# arm-pro-mini.net
KiCad netlist of a schematic drawn in EAGLE
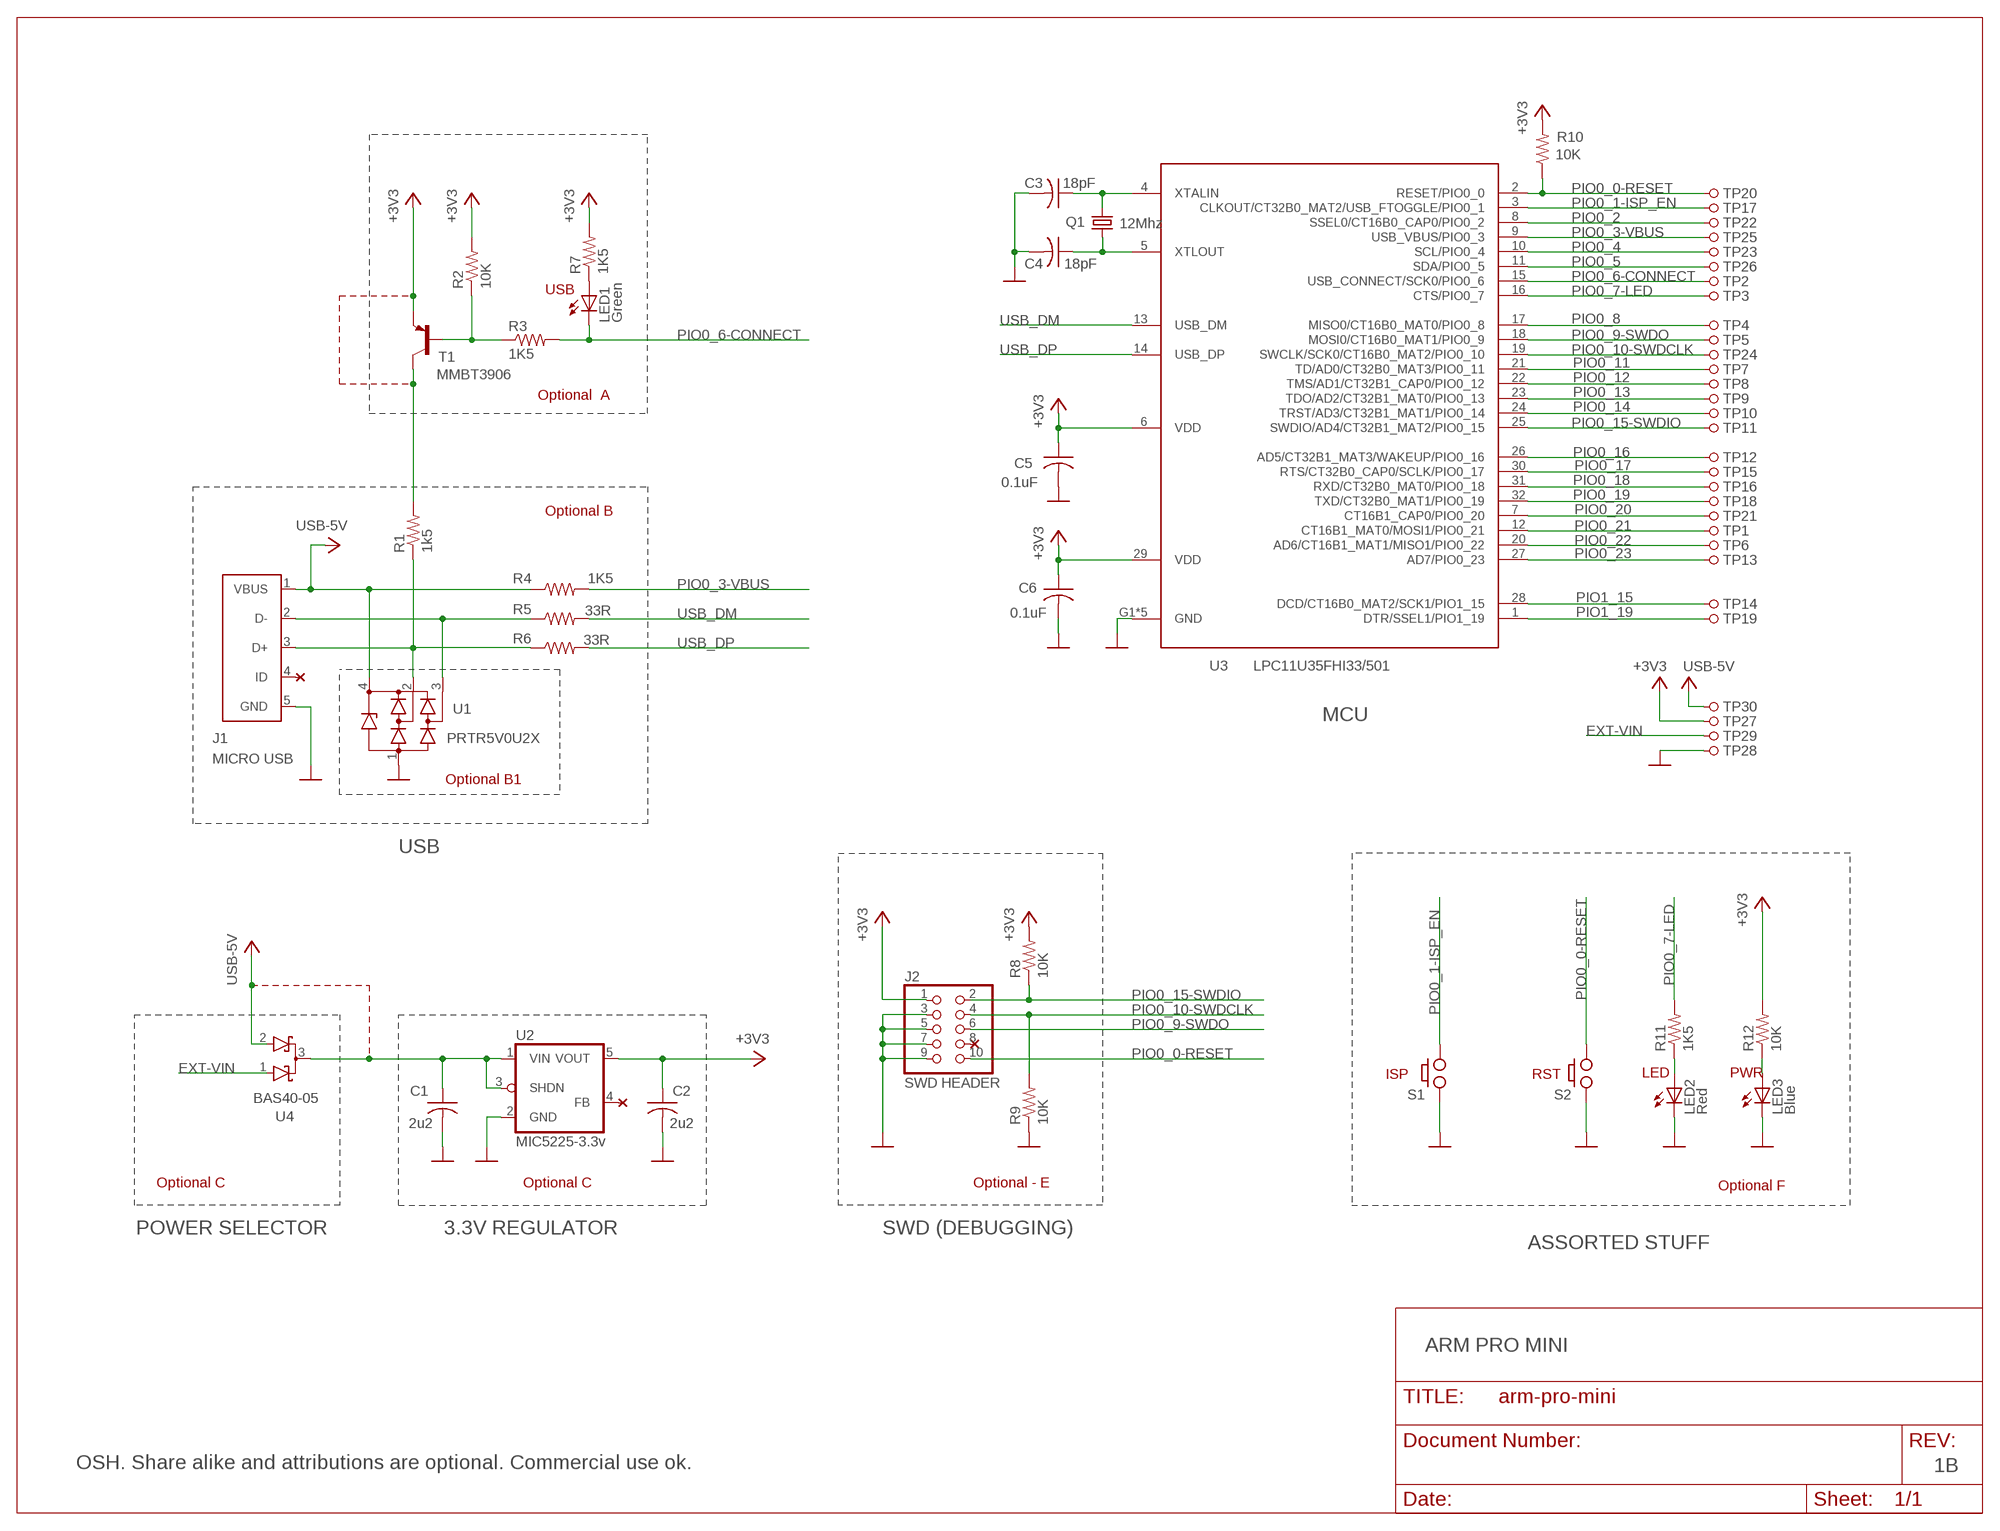
[diagram p0: schematic, sheet 1]

(export (version "E")
  (design (tool "Eeschema 10.0.6"))
  (components
    (comp (ref "C1")
      (value "2u2")
      (footprint "eagle-import:C0603K")
      (libsource (lib "eagle-import") (part "CAPACITORC0603K"))
    )
    (comp (ref "C2")
      (value "2u2")
      (footprint "eagle-import:C0603K")
      (libsource (lib "eagle-import") (part "CAPACITORC0603K"))
    )
    (comp (ref "C3")
      (value "18pF")
      (footprint "eagle-import:C0402K")
      (libsource (lib "eagle-import") (part "C-USC0402K"))
    )
    (comp (ref "C4")
      (value "18pF")
      (footprint "eagle-import:C0402K")
      (libsource (lib "eagle-import") (part "C-USC0402K"))
    )
    (comp (ref "C5")
      (value "0.1uF")
      (footprint "eagle-import:C0603K")
      (libsource (lib "eagle-import") (part "CAPACITORC0603K"))
    )
    (comp (ref "C6")
      (value "0.1uF")
      (footprint "eagle-import:C0603K")
      (libsource (lib "eagle-import") (part "CAPACITORC0603K"))
    )
    (comp (ref "J1")
      (value "MICRO USB")
      (footprint "eagle-import:USB-MICRO-ZX62RD-AB-5P8")
      (libsource (lib "eagle-import") (part "USB"))
    )
    (comp (ref "J2")
      (value "SWD HEADER")
      (footprint "eagle-import:SWD-HEADER")
      (libsource (lib "eagle-import") (part "SWD-HEADER"))
    )
    (comp (ref "LED1")
      (value "Green")
      (footprint "eagle-import:CHIP-LED0603")
      (libsource (lib "eagle-import") (part "LEDCHIP-LED0603"))
    )
    (comp (ref "LED2")
      (value "Red")
      (footprint "eagle-import:CHIP-LED0603")
      (libsource (lib "eagle-import") (part "LEDCHIP-LED0603"))
    )
    (comp (ref "LED3")
      (value "Blue")
      (footprint "eagle-import:CHIP-LED0603")
      (libsource (lib "eagle-import") (part "LEDCHIP-LED0603"))
    )
    (comp (ref "Q1")
      (value "12Mhz")
      (footprint "eagle-import:CRYSTAL")
      (libsource (lib "eagle-import") (part "CRYSTALCTS406"))
    )
    (comp (ref "R1")
      (value "1k5")
      (footprint "eagle-import:R0402")
      (libsource (lib "eagle-import") (part "R-US_R0402"))
    )
    (comp (ref "R2")
      (value "10K")
      (footprint "eagle-import:R0402")
      (libsource (lib "eagle-import") (part "R-US_R0402"))
    )
    (comp (ref "R3")
      (value "1K5")
      (footprint "eagle-import:R0402")
      (libsource (lib "eagle-import") (part "R-US_R0402"))
    )
    (comp (ref "R4")
      (value "1K5")
      (footprint "eagle-import:R0402")
      (libsource (lib "eagle-import") (part "R-US_R0402"))
    )
    (comp (ref "R5")
      (value "33R")
      (footprint "eagle-import:R0402")
      (libsource (lib "eagle-import") (part "R-US_R0402"))
    )
    (comp (ref "R6")
      (value "33R")
      (footprint "eagle-import:R0402")
      (libsource (lib "eagle-import") (part "R-US_R0402"))
    )
    (comp (ref "R7")
      (value "1K5")
      (footprint "eagle-import:R0402")
      (libsource (lib "eagle-import") (part "R-US_R0402"))
    )
    (comp (ref "R8")
      (value "10K")
      (footprint "eagle-import:R0402")
      (libsource (lib "eagle-import") (part "R-US_R0402"))
    )
    (comp (ref "R9")
      (value "10K")
      (footprint "eagle-import:R0402")
      (libsource (lib "eagle-import") (part "R-US_R0402"))
    )
    (comp (ref "R10")
      (value "10K")
      (footprint "eagle-import:R0402")
      (libsource (lib "eagle-import") (part "R-US_R0402"))
    )
    (comp (ref "R11")
      (value "1K5")
      (footprint "eagle-import:R0402")
      (libsource (lib "eagle-import") (part "R-US_R0402"))
    )
    (comp (ref "R12")
      (value "10K")
      (footprint "eagle-import:R0402")
      (libsource (lib "eagle-import") (part "R-US_R0402"))
    )
    (comp (ref "S1")
      (value "PUSH_BUTTON")
      (footprint "eagle-import:PUSH_BUTTON")
      (libsource (lib "eagle-import") (part "PUSH_BUTTON"))
    )
    (comp (ref "S2")
      (value "PUSH_BUTTON")
      (footprint "eagle-import:PUSH_BUTTON")
      (libsource (lib "eagle-import") (part "PUSH_BUTTON"))
    )
    (comp (ref "T1")
      (value "MMBT3906")
      (footprint "eagle-import:SOT23-BEC")
      (libsource (lib "eagle-import") (part "-PNP-SOT23-BECBC857B"))
    )
    (comp (ref "TP1")
      (value "HDR1")
      (footprint "eagle-import:1X01-SQUARE")
      (libsource (lib "eagle-import") (part "PINHD-1X1SQUARE"))
    )
    (comp (ref "TP2")
      (value "HDR1")
      (footprint "eagle-import:1X01")
      (libsource (lib "eagle-import") (part "PINHD-1X1"))
    )
    (comp (ref "TP3")
      (value "HDR1")
      (footprint "eagle-import:1X01")
      (libsource (lib "eagle-import") (part "PINHD-1X1"))
    )
    (comp (ref "TP4")
      (value "HDR1")
      (footprint "eagle-import:1X01")
      (libsource (lib "eagle-import") (part "PINHD-1X1"))
    )
    (comp (ref "TP5")
      (value "HDR1")
      (footprint "eagle-import:1X01")
      (libsource (lib "eagle-import") (part "PINHD-1X1"))
    )
    (comp (ref "TP6")
      (value "HDR1")
      (footprint "eagle-import:1X01")
      (libsource (lib "eagle-import") (part "PINHD-1X1"))
    )
    (comp (ref "TP7")
      (value "HDR1")
      (footprint "eagle-import:1X01")
      (libsource (lib "eagle-import") (part "PINHD-1X1"))
    )
    (comp (ref "TP8")
      (value "HDR1")
      (footprint "eagle-import:1X01")
      (libsource (lib "eagle-import") (part "PINHD-1X1"))
    )
    (comp (ref "TP9")
      (value "HDR1")
      (footprint "eagle-import:1X01")
      (libsource (lib "eagle-import") (part "PINHD-1X1"))
    )
    (comp (ref "TP10")
      (value "HDR1")
      (footprint "eagle-import:1X01")
      (libsource (lib "eagle-import") (part "PINHD-1X1"))
    )
    (comp (ref "TP11")
      (value "HDR1")
      (footprint "eagle-import:1X01")
      (libsource (lib "eagle-import") (part "PINHD-1X1"))
    )
    (comp (ref "TP12")
      (value "HDR1")
      (footprint "eagle-import:1X01")
      (libsource (lib "eagle-import") (part "PINHD-1X1"))
    )
    (comp (ref "TP13")
      (value "HDR1")
      (footprint "eagle-import:1X01")
      (libsource (lib "eagle-import") (part "PINHD-1X1"))
    )
    (comp (ref "TP14")
      (value "HDR1")
      (footprint "eagle-import:1X01")
      (libsource (lib "eagle-import") (part "PINHD-1X1"))
    )
    (comp (ref "TP15")
      (value "HDR1")
      (footprint "eagle-import:1X01")
      (libsource (lib "eagle-import") (part "PINHD-1X1"))
    )
    (comp (ref "TP16")
      (value "HDR1")
      (footprint "eagle-import:1X01")
      (libsource (lib "eagle-import") (part "PINHD-1X1"))
    )
    (comp (ref "TP17")
      (value "HDR1")
      (footprint "eagle-import:1X01")
      (libsource (lib "eagle-import") (part "PINHD-1X1"))
    )
    (comp (ref "TP18")
      (value "HDR1")
      (footprint "eagle-import:1X01")
      (libsource (lib "eagle-import") (part "PINHD-1X1"))
    )
    (comp (ref "TP19")
      (value "HDR1")
      (footprint "eagle-import:1X01")
      (libsource (lib "eagle-import") (part "PINHD-1X1"))
    )
    (comp (ref "TP20")
      (value "HDR1")
      (footprint "eagle-import:1X01")
      (libsource (lib "eagle-import") (part "PINHD-1X1"))
    )
    (comp (ref "TP21")
      (value "HDR1")
      (footprint "eagle-import:1X01")
      (libsource (lib "eagle-import") (part "PINHD-1X1"))
    )
    (comp (ref "TP22")
      (value "HDR1")
      (footprint "eagle-import:1X01")
      (libsource (lib "eagle-import") (part "PINHD-1X1"))
    )
    (comp (ref "TP23")
      (value "HDR1")
      (footprint "eagle-import:1X01")
      (libsource (lib "eagle-import") (part "PINHD-1X1"))
    )
    (comp (ref "TP24")
      (value "HDR1")
      (footprint "eagle-import:1X01")
      (libsource (lib "eagle-import") (part "PINHD-1X1"))
    )
    (comp (ref "TP25")
      (value "HDR1")
      (footprint "eagle-import:1X01")
      (libsource (lib "eagle-import") (part "PINHD-1X1"))
    )
    (comp (ref "TP26")
      (value "HDR1")
      (footprint "eagle-import:1X01")
      (libsource (lib "eagle-import") (part "PINHD-1X1"))
    )
    (comp (ref "TP27")
      (value "HDR1")
      (footprint "eagle-import:1X01")
      (libsource (lib "eagle-import") (part "PINHD-1X1"))
    )
    (comp (ref "TP28")
      (value "HDR1")
      (footprint "eagle-import:1X01")
      (libsource (lib "eagle-import") (part "PINHD-1X1"))
    )
    (comp (ref "TP29")
      (value "HDR1")
      (footprint "eagle-import:1X01")
      (libsource (lib "eagle-import") (part "PINHD-1X1"))
    )
    (comp (ref "TP30")
      (value "HDR1")
      (footprint "eagle-import:1X01")
      (libsource (lib "eagle-import") (part "PINHD-1X1"))
    )
    (comp (ref "U1")
      (value "PRTR5V0U2X")
      (footprint "eagle-import:SOT143B")
      (libsource (lib "eagle-import") (part "PRTR5V0U2X"))
    )
    (comp (ref "U2")
      (value "MIC5225-3.3v")
      (footprint "eagle-import:SOT25")
      (libsource (lib "eagle-import") (part "TC1015"))
    )
    (comp (ref "U3")
      (value "LPC11U35FHI33/501")
      (footprint "eagle-import:HVQFN33-5MM")
      (libsource (lib "eagle-import") (part "LPC11U35FHN33/501"))
    )
    (comp (ref "U4")
      (value "BAS40-05")
      (footprint "eagle-import:SOT23")
      (libsource (lib "eagle-import") (part "BAS40-05"))
    )
  )
  (nets
    (net (code "1") (name "+3V3") (class "Default")
      (node (ref "C2") (pin "1") (pinfunction "1_1") (pintype "passive"))
      (node (ref "C5") (pin "1") (pinfunction "1_1") (pintype "passive"))
      (node (ref "C6") (pin "1") (pinfunction "1_1") (pintype "passive"))
      (node (ref "J2") (pin "1") (pinfunction "1_1") (pintype "passive"))
      (node (ref "R10") (pin "2") (pinfunction "2_2") (pintype "passive"))
      (node (ref "R12") (pin "2") (pinfunction "2_2") (pintype "passive"))
      (node (ref "R2") (pin "2") (pinfunction "2_2") (pintype "passive"))
      (node (ref "R7") (pin "2") (pinfunction "2_2") (pintype "passive"))
      (node (ref "R8") (pin "2") (pinfunction "2_2") (pintype "passive"))
      (node (ref "T1") (pin "E") (pinfunction "E_E") (pintype "passive"))
      (node (ref "TP27") (pin "1") (pinfunction "1_1") (pintype "passive"))
      (node (ref "U2") (pin "5") (pinfunction "VOUT_5") (pintype "power_in"))
      (node (ref "U3") (pin "29") (pinfunction "VDD_29") (pintype "bidirectional"))
      (node (ref "U3") (pin "6") (pinfunction "VDD_6") (pintype "bidirectional"))
    )
    (net (code "2") (name "/EXT-VIN") (class "Default")
      (node (ref "TP29") (pin "1") (pinfunction "1_1") (pintype "passive"))
      (node (ref "U4") (pin "1") (pinfunction "A1_1") (pintype "passive"))
    )
    (net (code "3") (name "/PIO0_0-RESET") (class "Default")
      (node (ref "J2") (pin "10") (pinfunction "10_10") (pintype "passive"))
      (node (ref "R10") (pin "1") (pinfunction "1_1") (pintype "passive"))
      (node (ref "S2") (pin "B2") (pinfunction "2_B2") (pintype "passive"))
      (node (ref "TP20") (pin "1") (pinfunction "1_1") (pintype "passive"))
      (node (ref "U3") (pin "2") (pinfunction "RESET/PIO0_0_2") (pintype "bidirectional"))
    )
    (net (code "4") (name "/PIO0_1-ISP_EN") (class "Default")
      (node (ref "S1") (pin "B2") (pinfunction "2_B2") (pintype "passive"))
      (node (ref "TP17") (pin "1") (pinfunction "1_1") (pintype "passive"))
      (node (ref "U3") (pin "3") (pinfunction "CLKOUT/CT32B0_MAT2/USB_FTOGGLE/PIO0_1_3") (pintype "bidirectional"))
    )
    (net (code "5") (name "/PIO0_2") (class "Default")
      (node (ref "TP22") (pin "1") (pinfunction "1_1") (pintype "passive"))
      (node (ref "U3") (pin "8") (pinfunction "SSEL0/CT16B0_CAP0/PIO0_2_8") (pintype "bidirectional"))
    )
    (net (code "6") (name "/PIO0_3-VBUS") (class "Default")
      (node (ref "R4") (pin "2") (pinfunction "2_2") (pintype "passive"))
      (node (ref "TP25") (pin "1") (pinfunction "1_1") (pintype "passive"))
      (node (ref "U3") (pin "9") (pinfunction "USB_VBUS/PIO0_3_9") (pintype "bidirectional"))
    )
    (net (code "7") (name "/PIO0_4") (class "Default")
      (node (ref "TP23") (pin "1") (pinfunction "1_1") (pintype "passive"))
      (node (ref "U3") (pin "10") (pinfunction "SCL/PIO0_4_10") (pintype "bidirectional"))
    )
    (net (code "8") (name "/PIO0_5") (class "Default")
      (node (ref "TP26") (pin "1") (pinfunction "1_1") (pintype "passive"))
      (node (ref "U3") (pin "11") (pinfunction "SDA/PIO0_5_11") (pintype "bidirectional"))
    )
    (net (code "9") (name "/PIO0_6-CONNECT") (class "Default")
      (node (ref "LED1") (pin "C") (pinfunction "C_C") (pintype "passive"))
      (node (ref "R3") (pin "2") (pinfunction "2_2") (pintype "passive"))
      (node (ref "TP2") (pin "1") (pinfunction "1_1") (pintype "passive"))
      (node (ref "U3") (pin "15") (pinfunction "USB_CONNECT/SCK0/PIO0_6_15") (pintype "bidirectional"))
    )
    (net (code "10") (name "/PIO0_7-LED") (class "Default")
      (node (ref "R11") (pin "2") (pinfunction "2_2") (pintype "passive"))
      (node (ref "TP3") (pin "1") (pinfunction "1_1") (pintype "passive"))
      (node (ref "U3") (pin "16") (pinfunction "CTS/PIO0_7_16") (pintype "bidirectional"))
    )
    (net (code "11") (name "/PIO0_8") (class "Default")
      (node (ref "TP4") (pin "1") (pinfunction "1_1") (pintype "passive"))
      (node (ref "U3") (pin "17") (pinfunction "MISO0/CT16B0_MAT0/PIO0_8_17") (pintype "bidirectional"))
    )
    (net (code "12") (name "/PIO0_9-SWDO") (class "Default")
      (node (ref "J2") (pin "6") (pinfunction "6_6") (pintype "passive"))
      (node (ref "TP5") (pin "1") (pinfunction "1_1") (pintype "passive"))
      (node (ref "U3") (pin "18") (pinfunction "MOSI0/CT16B0_MAT1/PIO0_9_18") (pintype "bidirectional"))
    )
    (net (code "13") (name "/PIO0_10-SWDCLK") (class "Default")
      (node (ref "J2") (pin "4") (pinfunction "4_4") (pintype "passive"))
      (node (ref "R9") (pin "2") (pinfunction "2_2") (pintype "passive"))
      (node (ref "TP24") (pin "1") (pinfunction "1_1") (pintype "passive"))
      (node (ref "U3") (pin "19") (pinfunction "SWCLK/SCK0/CT16B0_MAT2/PIO0_10_19") (pintype "bidirectional"))
    )
    (net (code "14") (name "/PIO0_11") (class "Default")
      (node (ref "TP7") (pin "1") (pinfunction "1_1") (pintype "passive"))
      (node (ref "U3") (pin "21") (pinfunction "TD/AD0/CT32B0_MAT3/PIO0_11_21") (pintype "bidirectional"))
    )
    (net (code "15") (name "/PIO0_12") (class "Default")
      (node (ref "TP8") (pin "1") (pinfunction "1_1") (pintype "passive"))
      (node (ref "U3") (pin "22") (pinfunction "TMS/AD1/CT32B1_CAP0/PIO0_12_22") (pintype "bidirectional"))
    )
    (net (code "16") (name "/PIO0_13") (class "Default")
      (node (ref "TP9") (pin "1") (pinfunction "1_1") (pintype "passive"))
      (node (ref "U3") (pin "23") (pinfunction "TDO/AD2/CT32B1_MAT0/PIO0_13_23") (pintype "bidirectional"))
    )
    (net (code "17") (name "/PIO0_14") (class "Default")
      (node (ref "TP10") (pin "1") (pinfunction "1_1") (pintype "passive"))
      (node (ref "U3") (pin "24") (pinfunction "TRST/AD3/CT32B1_MAT1/PIO0_14_24") (pintype "bidirectional"))
    )
    (net (code "18") (name "/PIO0_15-SWDIO") (class "Default")
      (node (ref "J2") (pin "2") (pinfunction "2_2") (pintype "passive"))
      (node (ref "R8") (pin "1") (pinfunction "1_1") (pintype "passive"))
      (node (ref "TP11") (pin "1") (pinfunction "1_1") (pintype "passive"))
      (node (ref "U3") (pin "25") (pinfunction "SWDIO/AD4/CT32B1_MAT2/PIO0_15_25") (pintype "bidirectional"))
    )
    (net (code "19") (name "/PIO0_16") (class "Default")
      (node (ref "TP12") (pin "1") (pinfunction "1_1") (pintype "passive"))
      (node (ref "U3") (pin "26") (pinfunction "AD5/CT32B1_MAT3/WAKEUP/PIO0_16_26") (pintype "bidirectional"))
    )
    (net (code "20") (name "/PIO0_17") (class "Default")
      (node (ref "TP15") (pin "1") (pinfunction "1_1") (pintype "passive"))
      (node (ref "U3") (pin "30") (pinfunction "RTS/CT32B0_CAP0/SCLK/PIO0_17_30") (pintype "bidirectional"))
    )
    (net (code "21") (name "/PIO0_18") (class "Default")
      (node (ref "TP16") (pin "1") (pinfunction "1_1") (pintype "passive"))
      (node (ref "U3") (pin "31") (pinfunction "RXD/CT32B0_MAT0/PIO0_18_31") (pintype "bidirectional"))
    )
    (net (code "22") (name "/PIO0_19") (class "Default")
      (node (ref "TP18") (pin "1") (pinfunction "1_1") (pintype "passive"))
      (node (ref "U3") (pin "32") (pinfunction "TXD/CT32B0_MAT1/PIO0_19_32") (pintype "bidirectional"))
    )
    (net (code "23") (name "/PIO0_20") (class "Default")
      (node (ref "TP21") (pin "1") (pinfunction "1_1") (pintype "passive"))
      (node (ref "U3") (pin "7") (pinfunction "CT16B1_CAP0/PIO0_20_7") (pintype "bidirectional"))
    )
    (net (code "24") (name "/PIO0_21") (class "Default")
      (node (ref "TP1") (pin "1") (pinfunction "1_1") (pintype "passive"))
      (node (ref "U3") (pin "12") (pinfunction "CT16B1_MAT0/MOSI1/PIO0_21_12") (pintype "bidirectional"))
    )
    (net (code "25") (name "/PIO0_22") (class "Default")
      (node (ref "TP6") (pin "1") (pinfunction "1_1") (pintype "passive"))
      (node (ref "U3") (pin "20") (pinfunction "AD6/CT16B1_MAT1/MISO1/PIO0_22_20") (pintype "bidirectional"))
    )
    (net (code "26") (name "/PIO0_23") (class "Default")
      (node (ref "TP13") (pin "1") (pinfunction "1_1") (pintype "passive"))
      (node (ref "U3") (pin "27") (pinfunction "AD7/PIO0_23_27") (pintype "bidirectional"))
    )
    (net (code "27") (name "/PIO1_15") (class "Default")
      (node (ref "TP14") (pin "1") (pinfunction "1_1") (pintype "passive"))
      (node (ref "U3") (pin "28") (pinfunction "DCD/CT16B0_MAT2/SCK1/PIO1_15_28") (pintype "bidirectional"))
    )
    (net (code "28") (name "/PIO1_19") (class "Default")
      (node (ref "TP19") (pin "1") (pinfunction "1_1") (pintype "passive"))
      (node (ref "U3") (pin "1") (pinfunction "DTR/SSEL1/PIO1_19_1") (pintype "bidirectional"))
    )
    (net (code "29") (name "/USB_DM") (class "Default")
      (node (ref "R5") (pin "2") (pinfunction "2_2") (pintype "passive"))
      (node (ref "U3") (pin "13") (pinfunction "USB_DM_13") (pintype "bidirectional"))
    )
    (net (code "30") (name "/USB_DP") (class "Default")
      (node (ref "R6") (pin "2") (pinfunction "2_2") (pintype "passive"))
      (node (ref "U3") (pin "14") (pinfunction "USB_DP_14") (pintype "bidirectional"))
    )
    (net (code "31") (name "GND") (class "Default")
      (node (ref "C1") (pin "2") (pinfunction "2_2") (pintype "passive"))
      (node (ref "C2") (pin "2") (pinfunction "2_2") (pintype "passive"))
      (node (ref "C3") (pin "2") (pinfunction "2_2") (pintype "passive"))
      (node (ref "C4") (pin "2") (pinfunction "2_2") (pintype "passive"))
      (node (ref "C5") (pin "2") (pinfunction "2_2") (pintype "passive"))
      (node (ref "C6") (pin "2") (pinfunction "2_2") (pintype "passive"))
      (node (ref "J1") (pin "5") (pinfunction "GND_5") (pintype "bidirectional"))
      (node (ref "J2") (pin "3") (pinfunction "3_3") (pintype "passive"))
      (node (ref "J2") (pin "5") (pinfunction "5_5") (pintype "passive"))
      (node (ref "J2") (pin "7") (pinfunction "7_7") (pintype "passive"))
      (node (ref "J2") (pin "9") (pinfunction "9_9") (pintype "passive"))
      (node (ref "LED2") (pin "C") (pinfunction "C_C") (pintype "passive"))
      (node (ref "LED3") (pin "C") (pinfunction "C_C") (pintype "passive"))
      (node (ref "R9") (pin "1") (pinfunction "1_1") (pintype "passive"))
      (node (ref "S1") (pin "A1") (pinfunction "1_A1") (pintype "passive"))
      (node (ref "S2") (pin "A1") (pinfunction "1_A1") (pintype "passive"))
      (node (ref "TP28") (pin "1") (pinfunction "1_1") (pintype "passive"))
      (node (ref "U1") (pin "1") (pinfunction "GND_1") (pintype "passive"))
      (node (ref "U2") (pin "2") (pinfunction "GND_2") (pintype "power_in"))
      (node (ref "U3") (pin "G1") (pinfunction "GND_G1") (pintype "bidirectional"))
      (node (ref "U3") (pin "G2") (pinfunction "GND_G2") (pintype "bidirectional"))
      (node (ref "U3") (pin "G3") (pinfunction "GND_G3") (pintype "bidirectional"))
      (node (ref "U3") (pin "G4") (pinfunction "GND_G4") (pintype "bidirectional"))
      (node (ref "U3") (pin "TAB") (pinfunction "GND_TAB") (pintype "bidirectional"))
    )
    (net (code "32") (name "Net-(J1-D+)") (class "Default")
      (node (ref "J1") (pin "3") (pinfunction "D+_3") (pintype "bidirectional"))
      (node (ref "R1") (pin "1") (pinfunction "1_1") (pintype "passive"))
      (node (ref "R6") (pin "1") (pinfunction "1_1") (pintype "passive"))
      (node (ref "U1") (pin "2") (pinfunction "IO1_2") (pintype "passive"))
    )
    (net (code "33") (name "Net-(J1-D-)") (class "Default")
      (node (ref "J1") (pin "2") (pinfunction "D-_2") (pintype "bidirectional"))
      (node (ref "R5") (pin "1") (pinfunction "1_1") (pintype "passive"))
      (node (ref "U1") (pin "3") (pinfunction "IO2_3") (pintype "passive"))
    )
    (net (code "34") (name "Net-(LED1-PadA)") (class "Default")
      (node (ref "LED1") (pin "A") (pinfunction "A_A") (pintype "passive"))
      (node (ref "R7") (pin "1") (pinfunction "1_1") (pintype "passive"))
    )
    (net (code "35") (name "Net-(LED2-PadA)") (class "Default")
      (node (ref "LED2") (pin "A") (pinfunction "A_A") (pintype "passive"))
      (node (ref "R11") (pin "1") (pinfunction "1_1") (pintype "passive"))
    )
    (net (code "36") (name "Net-(LED3-PadA)") (class "Default")
      (node (ref "LED3") (pin "A") (pinfunction "A_A") (pintype "passive"))
      (node (ref "R12") (pin "1") (pinfunction "1_1") (pintype "passive"))
    )
    (net (code "37") (name "Net-(Q1-2)") (class "Default")
      (node (ref "C3") (pin "1") (pinfunction "1_1") (pintype "passive"))
      (node (ref "Q1") (pin "3") (pinfunction "2_3") (pintype "passive"))
      (node (ref "U3") (pin "4") (pinfunction "XTALIN_4") (pintype "bidirectional"))
    )
    (net (code "38") (name "Net-(R1-Pad2)") (class "Default")
      (node (ref "R1") (pin "2") (pinfunction "2_2") (pintype "passive"))
      (node (ref "T1") (pin "C") (pinfunction "C_C") (pintype "passive"))
    )
    (net (code "39") (name "Net-(R2-Pad1)") (class "Default")
      (node (ref "R2") (pin "1") (pinfunction "1_1") (pintype "passive"))
      (node (ref "R3") (pin "1") (pinfunction "1_1") (pintype "passive"))
      (node (ref "T1") (pin "B") (pinfunction "B_B") (pintype "passive"))
    )
    (net (code "40") (name "Net-(U2-SHDN)") (class "Default")
      (node (ref "C1") (pin "1") (pinfunction "1_1") (pintype "passive"))
      (node (ref "U2") (pin "1") (pinfunction "VIN_1") (pintype "power_in"))
      (node (ref "U2") (pin "3") (pinfunction "SHDN_3") (pintype "input"))
      (node (ref "U4") (pin "3") (pinfunction "C_3") (pintype "passive"))
    )
    (net (code "41") (name "Net-(U3-XTLOUT)") (class "Default")
      (node (ref "C4") (pin "1") (pinfunction "1_1") (pintype "passive"))
      (node (ref "Q1") (pin "1") (pinfunction "1_1") (pintype "passive"))
      (node (ref "U3") (pin "5") (pinfunction "XTLOUT_5") (pintype "bidirectional"))
    )
    (net (code "42") (name "USB-5V") (class "Default")
      (node (ref "J1") (pin "1") (pinfunction "VBUS_1") (pintype "bidirectional"))
      (node (ref "R4") (pin "1") (pinfunction "1_1") (pintype "passive"))
      (node (ref "TP30") (pin "1") (pinfunction "1_1") (pintype "passive"))
      (node (ref "U1") (pin "4") (pinfunction "VCC_4") (pintype "passive"))
      (node (ref "U4") (pin "2") (pinfunction "A2_2") (pintype "passive"))
    )
    (net (code "43") (name "unconnected-(J1-ID-Pad4)") (class "Default")
      (node (ref "J1") (pin "4") (pinfunction "ID_4") (pintype "bidirectional"))
    )
    (net (code "44") (name "unconnected-(J2-Pad8)") (class "Default")
      (node (ref "J2") (pin "8") (pinfunction "8_8") (pintype "passive"))
    )
    (net (code "45") (name "unconnected-(U2-FB-Pad4)") (class "Default")
      (node (ref "U2") (pin "4") (pinfunction "FB_4") (pintype "passive"))
    )
  )
)
